# RaumluftsensorC3.net
KiCad netlist of a schematic drawn in Altium Designer
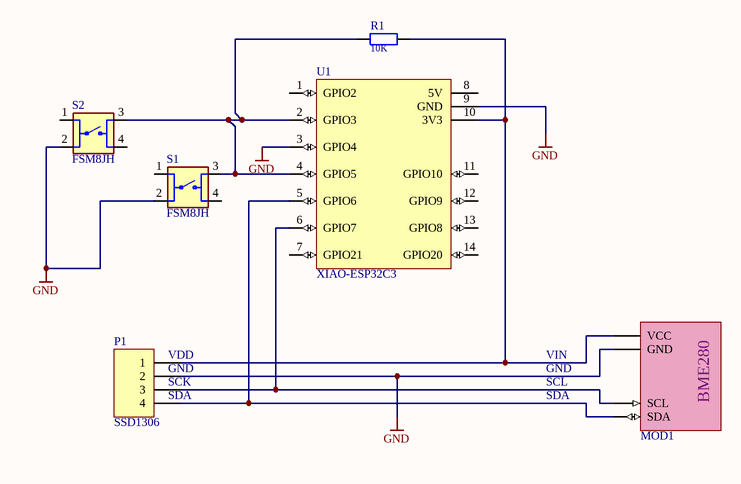
[diagram p0: RaumluftsensorC3.SchDoc]

(export (version "E")
  (design (tool "Eeschema 10.0.6"))
  (components
    (comp (ref "MOD1")
      (value "BME280")
      (footprint "BME280")
      (description "Bosch BME280 Module GY-BME280-3.3")
      (fields (field (name "PUBLISHER") "Michael Kupfner"))
      (libsource (lib "HTLinn_Miscellaneous") (part "BME280"))
    )
    (comp (ref "P1")
      (value "SSD1306")
      (footprint "HDR1X4")
      (description "OLED SSD1306 - Display")
      (fields (field (name "PUBLISHER") "Altium Limited"))
      (libsource (lib "Miscellaneous Connectors") (part "Header 4"))
    )
    (comp (ref "R1")
      (value "10K")
      (footprint "R_0207/RM4")
      (description "Resistor")
      (libsource (lib "HTLInn_RLCQ") (part "R"))
    )
    (comp (ref "S1")
      (value "FSM8JH")
      (footprint "SW_FSM8JH")
      (description "Tactile Switch SPST-NO Top Actuated Through Hole")
      (fields (field (name "MF") "TE Connectivity"))
      (libsource (lib "FSM8JH") (part "FSM8JH"))
    )
    (comp (ref "S2")
      (value "FSM8JH")
      (footprint "SW_FSM8JH")
      (description "Tactile Switch SPST-NO Top Actuated Through Hole")
      (fields (field (name "MF") "TE Connectivity"))
      (libsource (lib "FSM8JH") (part "FSM8JH"))
    )
    (comp (ref "U1")
      (value "XIAO-ESP32C3")
      (footprint "PCBComponent_1")
      (libsource (lib "XIAO ESP32C3") (part "XIAO-ESP32C3"))
    )
  )
  (nets
    (net (code "1") (name "GND") (class "Default")
      (node (ref "MOD1") (pin "2") (pinfunction "GND_2") (pintype "power_in"))
      (node (ref "P1") (pin "2") (pinfunction "2_2") (pintype "passive"))
      (node (ref "S1") (pin "2") (pinfunction "2_2") (pintype "passive"))
      (node (ref "S2") (pin "2") (pinfunction "2_2") (pintype "passive"))
      (node (ref "U1") (pin "3") (pinfunction "GPIO4_3") (pintype "bidirectional"))
      (node (ref "U1") (pin "9") (pinfunction "GND_9") (pintype "power_in"))
    )
    (net (code "2") (name "Net-(MOD1-SCL)") (class "Default")
      (node (ref "MOD1") (pin "3") (pinfunction "SCL_3") (pintype "input"))
      (node (ref "P1") (pin "3") (pinfunction "3_3") (pintype "passive"))
      (node (ref "U1") (pin "6") (pinfunction "GPIO7_6") (pintype "bidirectional"))
    )
    (net (code "3") (name "Net-(MOD1-SDA)") (class "Default")
      (node (ref "MOD1") (pin "4") (pinfunction "SDA_4") (pintype "bidirectional"))
      (node (ref "P1") (pin "4") (pinfunction "4_4") (pintype "passive"))
      (node (ref "U1") (pin "5") (pinfunction "GPIO6_5") (pintype "bidirectional"))
    )
    (net (code "4") (name "Net-(MOD1-VCC)") (class "Default")
      (node (ref "MOD1") (pin "1") (pinfunction "VCC_1") (pintype "power_in"))
      (node (ref "P1") (pin "1") (pinfunction "1_1") (pintype "passive"))
      (node (ref "R1") (pin "1") (pinfunction "1_1") (pintype "passive"))
      (node (ref "U1") (pin "10") (pinfunction "3V3_10") (pintype "power_in"))
    )
    (net (code "5") (name "Net-(U1-GPIO3)") (class "Default")
      (node (ref "R1") (pin "2") (pinfunction "2_2") (pintype "passive"))
      (node (ref "S1") (pin "3") (pinfunction "3_3") (pintype "passive"))
      (node (ref "S2") (pin "3") (pinfunction "3_3") (pintype "passive"))
      (node (ref "U1") (pin "2") (pinfunction "GPIO3_2") (pintype "bidirectional"))
      (node (ref "U1") (pin "4") (pinfunction "GPIO5_4") (pintype "bidirectional"))
    )
    (net (code "6") (name "unconnected-(S1-Pad1)") (class "Default")
      (node (ref "S1") (pin "1") (pinfunction "1_1") (pintype "passive"))
    )
    (net (code "7") (name "unconnected-(S1-Pad4)") (class "Default")
      (node (ref "S1") (pin "4") (pinfunction "4_4") (pintype "passive"))
    )
    (net (code "8") (name "unconnected-(S2-Pad1)") (class "Default")
      (node (ref "S2") (pin "1") (pinfunction "1_1") (pintype "passive"))
    )
    (net (code "9") (name "unconnected-(S2-Pad4)") (class "Default")
      (node (ref "S2") (pin "4") (pinfunction "4_4") (pintype "passive"))
    )
    (net (code "10") (name "unconnected-(U1-5V-Pad8)") (class "Default")
      (node (ref "U1") (pin "8") (pinfunction "5V_8") (pintype "power_in"))
    )
    (net (code "11") (name "unconnected-(U1-GPIO2-Pad1)") (class "Default")
      (node (ref "U1") (pin "1") (pinfunction "GPIO2_1") (pintype "bidirectional"))
    )
    (net (code "12") (name "unconnected-(U1-GPIO8-Pad13)") (class "Default")
      (node (ref "U1") (pin "13") (pinfunction "GPIO8_13") (pintype "bidirectional"))
    )
    (net (code "13") (name "unconnected-(U1-GPIO9-Pad12)") (class "Default")
      (node (ref "U1") (pin "12") (pinfunction "GPIO9_12") (pintype "bidirectional"))
    )
    (net (code "14") (name "unconnected-(U1-GPIO10-Pad11)") (class "Default")
      (node (ref "U1") (pin "11") (pinfunction "GPIO10_11") (pintype "bidirectional"))
    )
    (net (code "15") (name "unconnected-(U1-GPIO20-Pad14)") (class "Default")
      (node (ref "U1") (pin "14") (pinfunction "GPIO20_14") (pintype "bidirectional"))
    )
    (net (code "16") (name "unconnected-(U1-GPIO21-Pad7)") (class "Default")
      (node (ref "U1") (pin "7") (pinfunction "GPIO21_7") (pintype "bidirectional"))
    )
  )
)
